# DRL_Controller.net
KiCad netlist of a schematic drawn in EAGLE
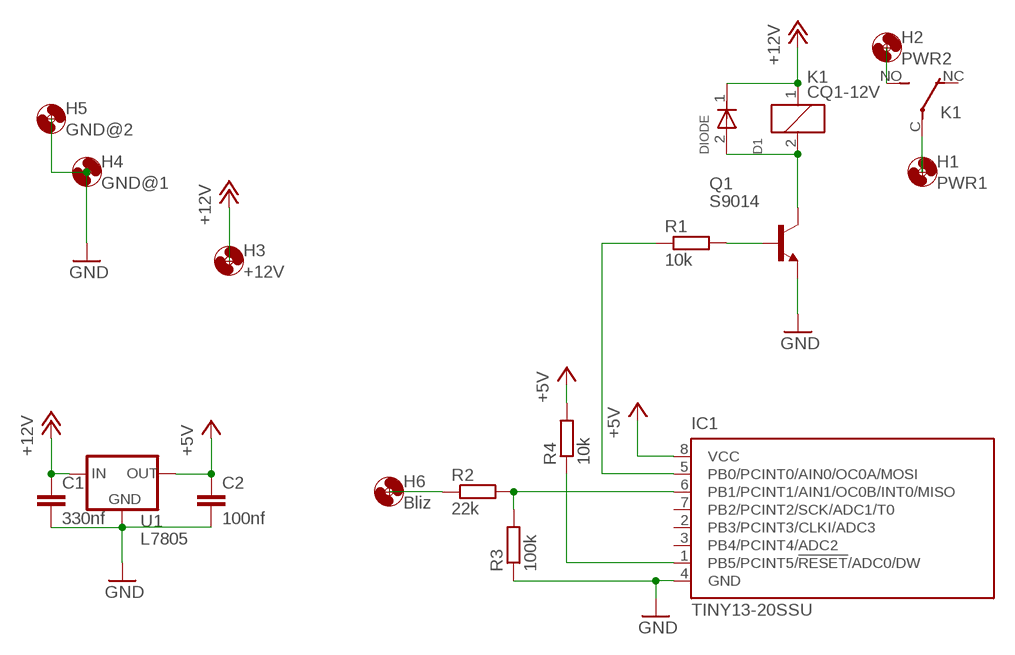
[diagram p0: schematic, sheet 1]

(export (version "E")
  (design (tool "Eeschema 10.0.6"))
  (components
    (comp (ref "C1")
      (value "330nf")
      (footprint "eagle-import:C0805")
      (libsource (lib "eagle-import") (part "C-EUC0805"))
    )
    (comp (ref "C2")
      (value "100nf")
      (footprint "eagle-import:C0805")
      (libsource (lib "eagle-import") (part "C-EUC0805"))
    )
    (comp (ref "D1")
      (value "DIODE")
      (footprint "eagle-import:SOD80")
      (libsource (lib "eagle-import") (part "DIODE"))
    )
    (comp (ref "H1")
      (value "PWR1")
      (footprint "eagle-import:3,0")
      (libsource (lib "eagle-import") (part "MOUNT-HOLE3.0"))
    )
    (comp (ref "H2")
      (value "PWR2")
      (footprint "eagle-import:3,0")
      (libsource (lib "eagle-import") (part "MOUNT-HOLE3.0"))
    )
    (comp (ref "H3")
      (value "+12V")
      (footprint "eagle-import:2,8")
      (libsource (lib "eagle-import") (part "MOUNT-HOLE2.8"))
    )
    (comp (ref "H4")
      (value "GND@1")
      (footprint "eagle-import:2,8")
      (libsource (lib "eagle-import") (part "MOUNT-HOLE2.8"))
    )
    (comp (ref "H5")
      (value "GND@2")
      (footprint "eagle-import:3,0")
      (libsource (lib "eagle-import") (part "MOUNT-HOLE3.0"))
    )
    (comp (ref "H6")
      (value "Bliz")
      (footprint "eagle-import:2,8")
      (libsource (lib "eagle-import") (part "MOUNT-HOLE2.8"))
    )
    (comp (ref "IC1")
      (value "TINY13-20SSU")
      (footprint "eagle-import:8S1")
      (fields (field (name "MPN") "ATTINY13-20SSU"))
      (libsource (lib "eagle-import") (part "TINY13SSU-20"))
    )
    (comp (ref "K1")
      (value "CQ1-12V")
      (footprint "eagle-import:CQ1")
      (libsource (lib "eagle-import") (part "CQ1-12V"))
    )
    (comp (ref "Q1")
      (value "S9014")
      (footprint "eagle-import:TO92")
      (libsource (lib "eagle-import") (part "2N3904"))
    )
    (comp (ref "R1")
      (value "10k")
      (footprint "eagle-import:R0805")
      (libsource (lib "eagle-import") (part "R-EU_R0805"))
    )
    (comp (ref "R2")
      (value "22k")
      (footprint "eagle-import:R0805")
      (libsource (lib "eagle-import") (part "R-EU_R0805"))
    )
    (comp (ref "R3")
      (value "100k")
      (footprint "eagle-import:R0805")
      (libsource (lib "eagle-import") (part "R-EU_R0805"))
    )
    (comp (ref "R4")
      (value "10k")
      (footprint "eagle-import:R0805")
      (libsource (lib "eagle-import") (part "R-EU_R0805"))
    )
    (comp (ref "U1")
      (value "L7805")
      (footprint "eagle-import:TO263")
      (libsource (lib "eagle-import") (part "L78XX/TO263"))
    )
  )
  (nets
    (net (code "1") (name "+5V") (class "Default")
      (node (ref "C2") (pin "1") (pinfunction "1_1") (pintype "passive"))
      (node (ref "IC1") (pin "8") (pinfunction "VCC_8") (pintype "power_in"))
      (node (ref "R4") (pin "2") (pinfunction "2_2") (pintype "passive"))
      (node (ref "U1") (pin "2") (pinfunction "OUT_2") (pintype "passive"))
    )
    (net (code "2") (name "+12V") (class "Default")
      (node (ref "C1") (pin "1") (pinfunction "1_1") (pintype "passive"))
      (node (ref "D1") (pin "1") (pinfunction "KATOD_1") (pintype "power_in"))
      (node (ref "H3") (pin "P$1") (pinfunction "P$1_P$1") (pintype "bidirectional"))
      (node (ref "K1") (pin "1") (pinfunction "1_1") (pintype "passive"))
      (node (ref "U1") (pin "1") (pinfunction "IN_1") (pintype "input"))
    )
    (net (code "3") (name "GND") (class "Default")
      (node (ref "C1") (pin "2") (pinfunction "2_2") (pintype "passive"))
      (node (ref "C2") (pin "2") (pinfunction "2_2") (pintype "passive"))
      (node (ref "H4") (pin "P$1") (pinfunction "P$1_P$1") (pintype "bidirectional"))
      (node (ref "H5") (pin "P$1") (pinfunction "P$1_P$1") (pintype "bidirectional"))
      (node (ref "IC1") (pin "4") (pinfunction "GND_4") (pintype "power_in"))
      (node (ref "Q1") (pin "3") (pinfunction "E_3") (pintype "passive"))
      (node (ref "R3") (pin "1") (pinfunction "1_1") (pintype "passive"))
      (node (ref "U1") (pin "3") (pinfunction "GND_3") (pintype "input"))
    )
    (net (code "4") (name "Net-(D1-ANOD)") (class "Default")
      (node (ref "D1") (pin "2") (pinfunction "ANOD_2") (pintype "power_in"))
      (node (ref "K1") (pin "2") (pinfunction "2_2") (pintype "passive"))
      (node (ref "Q1") (pin "1") (pinfunction "C_1") (pintype "passive"))
    )
    (net (code "5") (name "Net-(H6-PadP$1)") (class "Default")
      (node (ref "H6") (pin "P$1") (pinfunction "P$1_P$1") (pintype "bidirectional"))
      (node (ref "R2") (pin "1") (pinfunction "1_1") (pintype "passive"))
    )
    (net (code "6") (name "Net-(IC1-PB0{slash}PCINT0{slash}AIN0{slash}OC0A{slash}MOSI)") (class "Default")
      (node (ref "IC1") (pin "5") (pinfunction "PB0/PCINT0/AIN0/OC0A/MOSI_5") (pintype "bidirectional"))
      (node (ref "R1") (pin "1") (pinfunction "1_1") (pintype "passive"))
    )
    (net (code "7") (name "Net-(IC1-PB1{slash}PCINT1{slash}AIN1{slash}OC0B{slash}INT0{slash}MISO)") (class "Default")
      (node (ref "IC1") (pin "6") (pinfunction "PB1/PCINT1/AIN1/OC0B/INT0/MISO_6") (pintype "bidirectional"))
      (node (ref "R2") (pin "2") (pinfunction "2_2") (pintype "passive"))
      (node (ref "R3") (pin "2") (pinfunction "2_2") (pintype "passive"))
    )
    (net (code "8") (name "Net-(IC1-PB5{slash}PCINT5{slash}~{RESET}{slash}ADC0{slash}DW)") (class "Default")
      (node (ref "IC1") (pin "1") (pinfunction "PB5/PCINT5/~{RESET}/ADC0/DW_1") (pintype "bidirectional"))
      (node (ref "R4") (pin "1") (pinfunction "1_1") (pintype "passive"))
    )
    (net (code "9") (name "Net-(K1B-P)") (class "Default")
      (node (ref "H1") (pin "P$1") (pinfunction "P$1_P$1") (pintype "bidirectional"))
      (node (ref "K1") (pin "C") (pinfunction "P_C") (pintype "passive"))
    )
    (net (code "10") (name "Net-(K1B-S)") (class "Default")
      (node (ref "H2") (pin "P$1") (pinfunction "P$1_P$1") (pintype "bidirectional"))
      (node (ref "K1") (pin "NO") (pinfunction "S_NO") (pintype "passive"))
    )
    (net (code "11") (name "Net-(Q1-B)") (class "Default")
      (node (ref "Q1") (pin "2") (pinfunction "B_2") (pintype "passive"))
      (node (ref "R1") (pin "2") (pinfunction "2_2") (pintype "passive"))
    )
    (net (code "12") (name "unconnected-(IC1-PB2{slash}PCINT2{slash}SCK{slash}ADC1{slash}T0-Pad7)") (class "Default")
      (node (ref "IC1") (pin "7") (pinfunction "PB2/PCINT2/SCK/ADC1/T0_7") (pintype "bidirectional"))
    )
    (net (code "13") (name "unconnected-(IC1-PB3{slash}PCINT3{slash}CLKI{slash}ADC3-Pad2)") (class "Default")
      (node (ref "IC1") (pin "2") (pinfunction "PB3/PCINT3/CLKI/ADC3_2") (pintype "bidirectional"))
    )
    (net (code "14") (name "unconnected-(IC1-PB4{slash}PCINT4{slash}ADC2-Pad3)") (class "Default")
      (node (ref "IC1") (pin "3") (pinfunction "PB4/PCINT4/ADC2_3") (pintype "bidirectional"))
    )
    (net (code "15") (name "unconnected-(K1B-O-PadNC)") (class "Default")
      (node (ref "K1") (pin "NC") (pinfunction "O_NC") (pintype "passive"))
    )
  )
)
